# scales_old_new.net
KiCad netlist of a schematic drawn in EAGLE
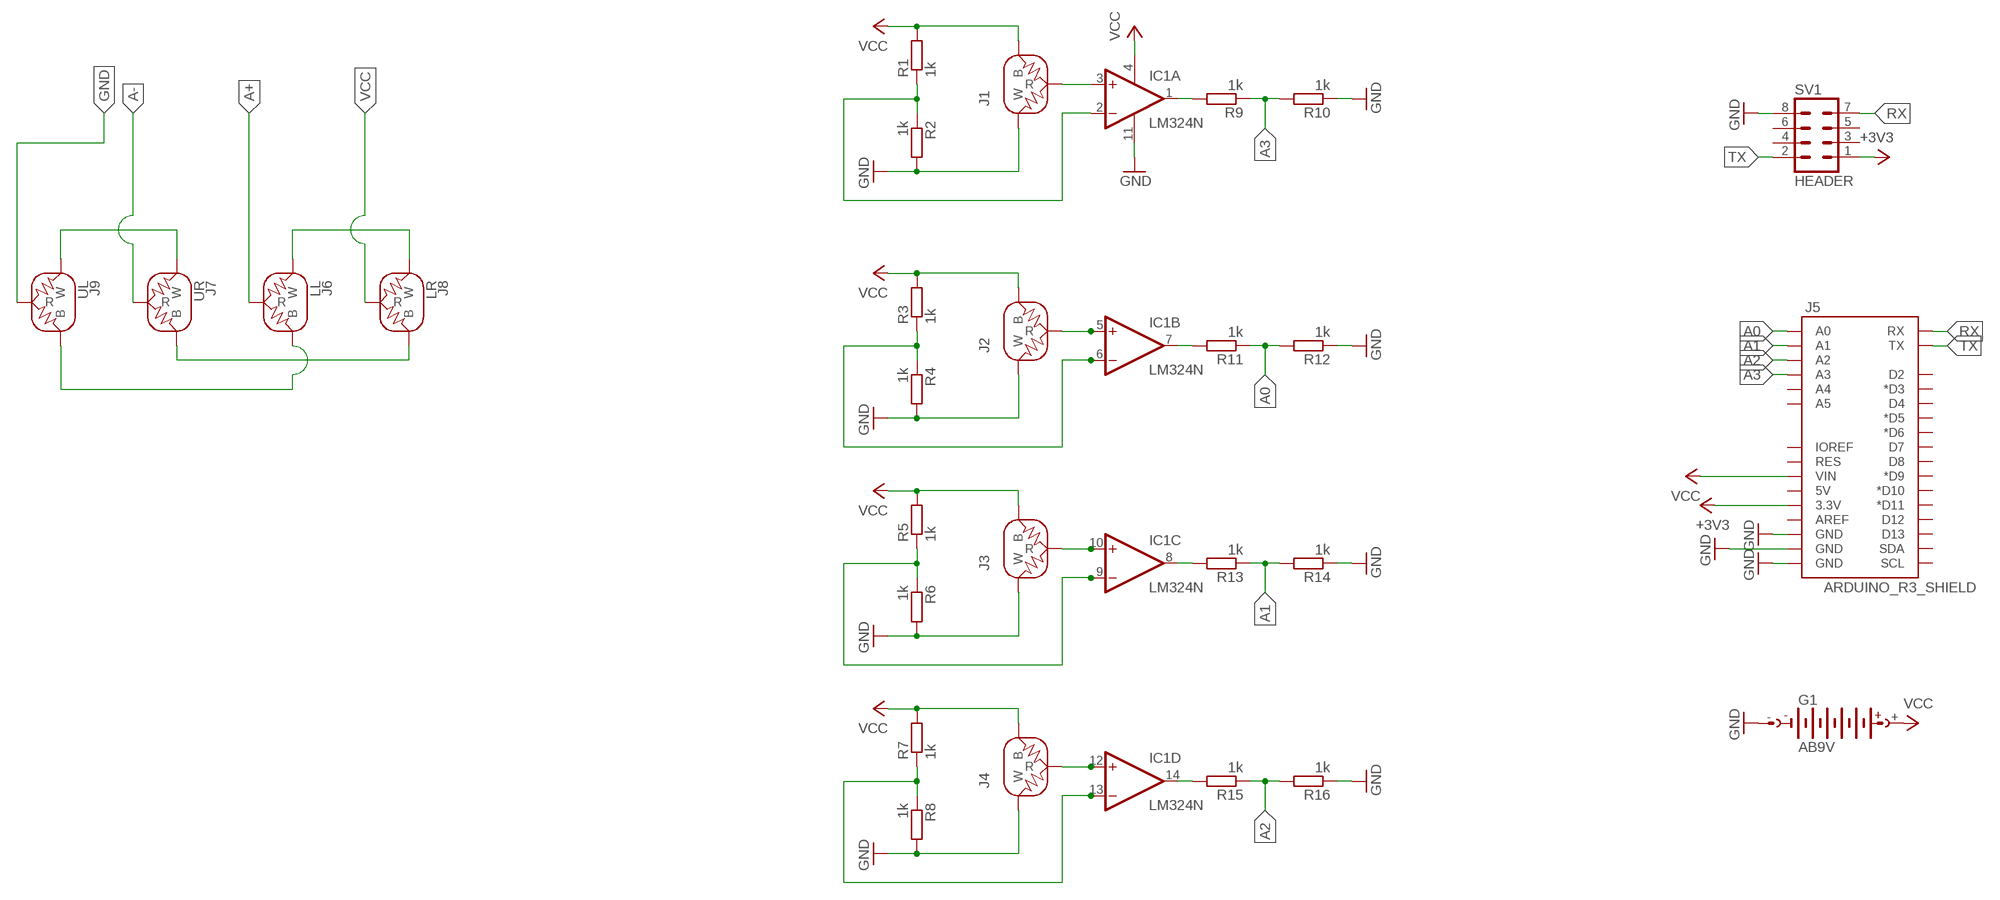
[diagram p0: schematic, sheet 1]

(export (version "E")
  (design (tool "Eeschema 10.0.6"))
  (components
    (comp (ref "G1")
      (value "AB9V")
      (footprint "eagle-import:AB9V")
      (fields (field (name "MF") "MULTICOMP") (field (name "MPN") "440005P"))
      (libsource (lib "eagle-import") (part "AB9V"))
    )
    (comp (ref "IC1")
      (value "LM324N")
      (footprint "eagle-import:DIL14")
      (fields
        (field (name "MF") "STMICROELECTRONICS")
        (field (name "MPN") "LM324AN")
        (field (name "OC_FARNELL") "1467654")
      )
      (libsource (lib "eagle-import") (part "LM324N"))
    )
    (comp (ref "J1")
      (value "LOAD_CELL1X03-PTH")
      (footprint "eagle-import:1X03")
      (libsource (lib "eagle-import") (part "LOAD_CELL1X03-PTH"))
    )
    (comp (ref "J2")
      (value "LOAD_CELL1X03-PTH")
      (footprint "eagle-import:1X03")
      (libsource (lib "eagle-import") (part "LOAD_CELL1X03-PTH"))
    )
    (comp (ref "J3")
      (value "LOAD_CELL1X03-PTH")
      (footprint "eagle-import:1X03")
      (libsource (lib "eagle-import") (part "LOAD_CELL1X03-PTH"))
    )
    (comp (ref "J4")
      (value "LOAD_CELL1X03-PTH")
      (footprint "eagle-import:1X03")
      (libsource (lib "eagle-import") (part "LOAD_CELL1X03-PTH"))
    )
    (comp (ref "J5")
      (value "ARDUINO_R3_SHIELD")
      (footprint "eagle-import:UNO_R3_SHIELD")
      (libsource (lib "eagle-import") (part "ARDUINO_R3_SHIELD"))
    )
    (comp (ref "J6")
      (value "LL")
      (footprint "eagle-import:1X03")
      (libsource (lib "eagle-import") (part "LOAD_CELL1X03-PTH"))
    )
    (comp (ref "J7")
      (value "UR")
      (footprint "eagle-import:1X03")
      (libsource (lib "eagle-import") (part "LOAD_CELL1X03-PTH"))
    )
    (comp (ref "J8")
      (value "LR")
      (footprint "eagle-import:1X03")
      (libsource (lib "eagle-import") (part "LOAD_CELL1X03-PTH"))
    )
    (comp (ref "J9")
      (value "UL")
      (footprint "eagle-import:1X03")
      (libsource (lib "eagle-import") (part "LOAD_CELL1X03-PTH"))
    )
    (comp (ref "R1")
      (value "1k")
      (footprint "eagle-import:0204_5")
      (fields (field (name "MF") "PANASONIC ELECTRONIC COMPONENTS") (field (name "MPN") "ERG1SJ102"))
      (libsource (lib "eagle-import") (part "R-EU_0204/5"))
    )
    (comp (ref "R2")
      (value "1k")
      (footprint "eagle-import:0204_5")
      (fields (field (name "MF") "PANASONIC ELECTRONIC COMPONENTS") (field (name "MPN") "ERG1SJ102"))
      (libsource (lib "eagle-import") (part "R-EU_0204/5"))
    )
    (comp (ref "R3")
      (value "1k")
      (footprint "eagle-import:0204_5")
      (fields (field (name "MF") "PANASONIC ELECTRONIC COMPONENTS") (field (name "MPN") "ERG1SJ102"))
      (libsource (lib "eagle-import") (part "R-EU_0204/5"))
    )
    (comp (ref "R4")
      (value "1k")
      (footprint "eagle-import:0204_5")
      (fields (field (name "MF") "PANASONIC ELECTRONIC COMPONENTS") (field (name "MPN") "ERG1SJ102"))
      (libsource (lib "eagle-import") (part "R-EU_0204/5"))
    )
    (comp (ref "R5")
      (value "1k")
      (footprint "eagle-import:0204_5")
      (fields (field (name "MF") "PANASONIC ELECTRONIC COMPONENTS") (field (name "MPN") "ERG1SJ102"))
      (libsource (lib "eagle-import") (part "R-EU_0204/5"))
    )
    (comp (ref "R6")
      (value "1k")
      (footprint "eagle-import:0204_5")
      (fields (field (name "MF") "PANASONIC ELECTRONIC COMPONENTS") (field (name "MPN") "ERG1SJ102"))
      (libsource (lib "eagle-import") (part "R-EU_0204/5"))
    )
    (comp (ref "R7")
      (value "1k")
      (footprint "eagle-import:0204_5")
      (fields (field (name "MF") "PANASONIC ELECTRONIC COMPONENTS") (field (name "MPN") "ERG1SJ102"))
      (libsource (lib "eagle-import") (part "R-EU_0204/5"))
    )
    (comp (ref "R8")
      (value "1k")
      (footprint "eagle-import:0204_5")
      (fields (field (name "MF") "PANASONIC ELECTRONIC COMPONENTS") (field (name "MPN") "ERG1SJ102"))
      (libsource (lib "eagle-import") (part "R-EU_0204/5"))
    )
    (comp (ref "R9")
      (value "1k")
      (footprint "eagle-import:0204_5")
      (fields (field (name "MF") "PANASONIC ELECTRONIC COMPONENTS") (field (name "MPN") "ERG1SJ102"))
      (libsource (lib "eagle-import") (part "R-EU_0204/5"))
    )
    (comp (ref "R10")
      (value "1k")
      (footprint "eagle-import:0204_5")
      (fields (field (name "MF") "PANASONIC ELECTRONIC COMPONENTS") (field (name "MPN") "ERG1SJ102"))
      (libsource (lib "eagle-import") (part "R-EU_0204/5"))
    )
    (comp (ref "R11")
      (value "1k")
      (footprint "eagle-import:0204_5")
      (fields (field (name "MF") "PANASONIC ELECTRONIC COMPONENTS") (field (name "MPN") "ERG1SJ102"))
      (libsource (lib "eagle-import") (part "R-EU_0204/5"))
    )
    (comp (ref "R12")
      (value "1k")
      (footprint "eagle-import:0204_5")
      (fields (field (name "MF") "PANASONIC ELECTRONIC COMPONENTS") (field (name "MPN") "ERG1SJ102"))
      (libsource (lib "eagle-import") (part "R-EU_0204/5"))
    )
    (comp (ref "R13")
      (value "1k")
      (footprint "eagle-import:0204_5")
      (fields (field (name "MF") "PANASONIC ELECTRONIC COMPONENTS") (field (name "MPN") "ERG1SJ102"))
      (libsource (lib "eagle-import") (part "R-EU_0204/5"))
    )
    (comp (ref "R14")
      (value "1k")
      (footprint "eagle-import:0204_5")
      (fields (field (name "MF") "PANASONIC ELECTRONIC COMPONENTS") (field (name "MPN") "ERG1SJ102"))
      (libsource (lib "eagle-import") (part "R-EU_0204/5"))
    )
    (comp (ref "R15")
      (value "1k")
      (footprint "eagle-import:0204_5")
      (fields (field (name "MF") "PANASONIC ELECTRONIC COMPONENTS") (field (name "MPN") "ERG1SJ102"))
      (libsource (lib "eagle-import") (part "R-EU_0204/5"))
    )
    (comp (ref "R16")
      (value "1k")
      (footprint "eagle-import:0204_5")
      (fields (field (name "MF") "PANASONIC ELECTRONIC COMPONENTS") (field (name "MPN") "ERG1SJ102"))
      (libsource (lib "eagle-import") (part "R-EU_0204/5"))
    )
    (comp (ref "SV1")
      (value "HEADER")
      (footprint "eagle-import:MA04-2")
      (fields
        (field (name "MF") "GLOBAL CONNECTOR TECHNOLOGY")
        (field (name "MPN") "BD060-08-A-N-0230-L-G")
        (field (name "OC_FARNELL") "1798806")
      )
      (libsource (lib "eagle-import") (part "MA04-2"))
    )
  )
  (nets
    (net (code "1") (name "+3V3") (class "Default")
      (node (ref "J5") (pin "3.3V") (pinfunction "3.3V_3.3V") (pintype "bidirectional"))
      (node (ref "SV1") (pin "1") (pinfunction "1_1") (pintype "passive"))
    )
    (net (code "2") (name "A+") (class "Default")
      (node (ref "J6") (pin "3") (pinfunction "R_3") (pintype "passive"))
    )
    (net (code "3") (name "A-") (class "Default")
      (node (ref "J7") (pin "3") (pinfunction "R_3") (pintype "passive"))
    )
    (net (code "4") (name "A0") (class "Default")
      (node (ref "J5") (pin "A0") (pinfunction "A0_A0") (pintype "bidirectional"))
      (node (ref "R11") (pin "1") (pinfunction "1_1") (pintype "passive"))
      (node (ref "R12") (pin "2") (pinfunction "2_2") (pintype "passive"))
    )
    (net (code "5") (name "A1") (class "Default")
      (node (ref "J5") (pin "A1") (pinfunction "A1_A1") (pintype "bidirectional"))
      (node (ref "R13") (pin "1") (pinfunction "1_1") (pintype "passive"))
      (node (ref "R14") (pin "2") (pinfunction "2_2") (pintype "passive"))
    )
    (net (code "6") (name "A2") (class "Default")
      (node (ref "J5") (pin "A2") (pinfunction "A2_A2") (pintype "bidirectional"))
      (node (ref "R15") (pin "1") (pinfunction "1_1") (pintype "passive"))
      (node (ref "R16") (pin "2") (pinfunction "2_2") (pintype "passive"))
    )
    (net (code "7") (name "A3") (class "Default")
      (node (ref "J5") (pin "A3") (pinfunction "A3_A3") (pintype "bidirectional"))
      (node (ref "R10") (pin "2") (pinfunction "2_2") (pintype "passive"))
      (node (ref "R9") (pin "1") (pinfunction "1_1") (pintype "passive"))
    )
    (net (code "8") (name "GND") (class "Default")
      (node (ref "G1") (pin "-") (pinfunction "-_-") (pintype "passive"))
      (node (ref "IC1") (pin "11") (pinfunction "V-_11") (pintype "power_in"))
      (node (ref "J1") (pin "2") (pinfunction "W_2") (pintype "passive"))
      (node (ref "J2") (pin "2") (pinfunction "W_2") (pintype "passive"))
      (node (ref "J3") (pin "2") (pinfunction "W_2") (pintype "passive"))
      (node (ref "J4") (pin "2") (pinfunction "W_2") (pintype "passive"))
      (node (ref "J5") (pin "GND@0") (pinfunction "GND_GND@0") (pintype "bidirectional"))
      (node (ref "J5") (pin "GND@1") (pinfunction "GND_GND@1") (pintype "bidirectional"))
      (node (ref "J5") (pin "GND@2") (pinfunction "GND_GND@2") (pintype "bidirectional"))
      (node (ref "J9") (pin "3") (pinfunction "R_3") (pintype "passive"))
      (node (ref "R10") (pin "1") (pinfunction "1_1") (pintype "passive"))
      (node (ref "R12") (pin "1") (pinfunction "1_1") (pintype "passive"))
      (node (ref "R14") (pin "1") (pinfunction "1_1") (pintype "passive"))
      (node (ref "R16") (pin "1") (pinfunction "1_1") (pintype "passive"))
      (node (ref "R2") (pin "2") (pinfunction "2_2") (pintype "passive"))
      (node (ref "R4") (pin "2") (pinfunction "2_2") (pintype "passive"))
      (node (ref "R6") (pin "2") (pinfunction "2_2") (pintype "passive"))
      (node (ref "R8") (pin "2") (pinfunction "2_2") (pintype "passive"))
      (node (ref "SV1") (pin "8") (pinfunction "8_8") (pintype "passive"))
    )
    (net (code "9") (name "Net-(IC1A-+IN)") (class "Default")
      (node (ref "IC1") (pin "3") (pinfunction "+IN_3") (pintype "input"))
      (node (ref "J1") (pin "3") (pinfunction "R_3") (pintype "passive"))
    )
    (net (code "10") (name "Net-(IC1A--IN)") (class "Default")
      (node (ref "IC1") (pin "2") (pinfunction "-IN_2") (pintype "input"))
      (node (ref "R1") (pin "1") (pinfunction "1_1") (pintype "passive"))
      (node (ref "R2") (pin "1") (pinfunction "1_1") (pintype "passive"))
    )
    (net (code "11") (name "Net-(IC1A-OUT)") (class "Default")
      (node (ref "IC1") (pin "1") (pinfunction "OUT_1") (pintype "output"))
      (node (ref "R9") (pin "2") (pinfunction "2_2") (pintype "passive"))
    )
    (net (code "12") (name "Net-(IC1B-+IN)") (class "Default")
      (node (ref "IC1") (pin "5") (pinfunction "+IN_5") (pintype "input"))
      (node (ref "J2") (pin "3") (pinfunction "R_3") (pintype "passive"))
    )
    (net (code "13") (name "Net-(IC1B--IN)") (class "Default")
      (node (ref "IC1") (pin "6") (pinfunction "-IN_6") (pintype "input"))
      (node (ref "R3") (pin "1") (pinfunction "1_1") (pintype "passive"))
      (node (ref "R4") (pin "1") (pinfunction "1_1") (pintype "passive"))
    )
    (net (code "14") (name "Net-(IC1B-OUT)") (class "Default")
      (node (ref "IC1") (pin "7") (pinfunction "OUT_7") (pintype "output"))
      (node (ref "R11") (pin "2") (pinfunction "2_2") (pintype "passive"))
    )
    (net (code "15") (name "Net-(IC1C-+IN)") (class "Default")
      (node (ref "IC1") (pin "10") (pinfunction "+IN_10") (pintype "input"))
      (node (ref "J3") (pin "3") (pinfunction "R_3") (pintype "passive"))
    )
    (net (code "16") (name "Net-(IC1C--IN)") (class "Default")
      (node (ref "IC1") (pin "9") (pinfunction "-IN_9") (pintype "input"))
      (node (ref "R5") (pin "1") (pinfunction "1_1") (pintype "passive"))
      (node (ref "R6") (pin "1") (pinfunction "1_1") (pintype "passive"))
    )
    (net (code "17") (name "Net-(IC1C-OUT)") (class "Default")
      (node (ref "IC1") (pin "8") (pinfunction "OUT_8") (pintype "output"))
      (node (ref "R13") (pin "2") (pinfunction "2_2") (pintype "passive"))
    )
    (net (code "18") (name "Net-(IC1D-+IN)") (class "Default")
      (node (ref "IC1") (pin "12") (pinfunction "+IN_12") (pintype "input"))
      (node (ref "J4") (pin "3") (pinfunction "R_3") (pintype "passive"))
    )
    (net (code "19") (name "Net-(IC1D--IN)") (class "Default")
      (node (ref "IC1") (pin "13") (pinfunction "-IN_13") (pintype "input"))
      (node (ref "R7") (pin "1") (pinfunction "1_1") (pintype "passive"))
      (node (ref "R8") (pin "1") (pinfunction "1_1") (pintype "passive"))
    )
    (net (code "20") (name "Net-(IC1D-OUT)") (class "Default")
      (node (ref "IC1") (pin "14") (pinfunction "OUT_14") (pintype "output"))
      (node (ref "R15") (pin "2") (pinfunction "2_2") (pintype "passive"))
    )
    (net (code "21") (name "Net-(J6-B)") (class "Default")
      (node (ref "J6") (pin "1") (pinfunction "B_1") (pintype "passive"))
      (node (ref "J9") (pin "1") (pinfunction "B_1") (pintype "passive"))
    )
    (net (code "22") (name "Net-(J6-W)") (class "Default")
      (node (ref "J6") (pin "2") (pinfunction "W_2") (pintype "passive"))
      (node (ref "J8") (pin "2") (pinfunction "W_2") (pintype "passive"))
    )
    (net (code "23") (name "Net-(J7-B)") (class "Default")
      (node (ref "J7") (pin "1") (pinfunction "B_1") (pintype "passive"))
      (node (ref "J8") (pin "1") (pinfunction "B_1") (pintype "passive"))
    )
    (net (code "24") (name "Net-(J7-W)") (class "Default")
      (node (ref "J7") (pin "2") (pinfunction "W_2") (pintype "passive"))
      (node (ref "J9") (pin "2") (pinfunction "W_2") (pintype "passive"))
    )
    (net (code "25") (name "RX") (class "Default")
      (node (ref "J5") (pin "RX") (pinfunction "RX_RX") (pintype "bidirectional"))
      (node (ref "SV1") (pin "7") (pinfunction "7_7") (pintype "passive"))
    )
    (net (code "26") (name "TX") (class "Default")
      (node (ref "J5") (pin "TX") (pinfunction "TX_TX") (pintype "bidirectional"))
      (node (ref "SV1") (pin "2") (pinfunction "2_2") (pintype "passive"))
    )
    (net (code "27") (name "VCC") (class "Default")
      (node (ref "G1") (pin "+") (pinfunction "+_+") (pintype "passive"))
      (node (ref "IC1") (pin "4") (pinfunction "V+_4") (pintype "power_in"))
      (node (ref "J1") (pin "1") (pinfunction "B_1") (pintype "passive"))
      (node (ref "J2") (pin "1") (pinfunction "B_1") (pintype "passive"))
      (node (ref "J3") (pin "1") (pinfunction "B_1") (pintype "passive"))
      (node (ref "J4") (pin "1") (pinfunction "B_1") (pintype "passive"))
      (node (ref "J5") (pin "VIN") (pinfunction "VIN_VIN") (pintype "bidirectional"))
      (node (ref "J8") (pin "3") (pinfunction "R_3") (pintype "passive"))
      (node (ref "R1") (pin "2") (pinfunction "2_2") (pintype "passive"))
      (node (ref "R3") (pin "2") (pinfunction "2_2") (pintype "passive"))
      (node (ref "R5") (pin "2") (pinfunction "2_2") (pintype "passive"))
      (node (ref "R7") (pin "2") (pinfunction "2_2") (pintype "passive"))
    )
    (net (code "28") (name "unconnected-(J5-*D3-PadD3)") (class "Default")
      (node (ref "J5") (pin "D3") (pinfunction "*D3_D3") (pintype "bidirectional"))
    )
    (net (code "29") (name "unconnected-(J5-*D5-PadD5)") (class "Default")
      (node (ref "J5") (pin "D5") (pinfunction "*D5_D5") (pintype "bidirectional"))
    )
    (net (code "30") (name "unconnected-(J5-*D6-PadD6)") (class "Default")
      (node (ref "J5") (pin "D6") (pinfunction "*D6_D6") (pintype "bidirectional"))
    )
    (net (code "31") (name "unconnected-(J5-*D9-PadD9)") (class "Default")
      (node (ref "J5") (pin "D9") (pinfunction "*D9_D9") (pintype "bidirectional"))
    )
    (net (code "32") (name "unconnected-(J5-*D10-PadD10)") (class "Default")
      (node (ref "J5") (pin "D10") (pinfunction "*D10_D10") (pintype "bidirectional"))
    )
    (net (code "33") (name "unconnected-(J5-*D11-PadD11)") (class "Default")
      (node (ref "J5") (pin "D11") (pinfunction "*D11_D11") (pintype "bidirectional"))
    )
    (net (code "34") (name "unconnected-(J5-Pad5V)") (class "Default")
      (node (ref "J5") (pin "5V") (pinfunction "5V_5V") (pintype "bidirectional"))
    )
    (net (code "35") (name "unconnected-(J5-PadA4)") (class "Default")
      (node (ref "J5") (pin "A4") (pinfunction "A4_A4") (pintype "bidirectional"))
    )
    (net (code "36") (name "unconnected-(J5-PadA5)") (class "Default")
      (node (ref "J5") (pin "A5") (pinfunction "A5_A5") (pintype "bidirectional"))
    )
    (net (code "37") (name "unconnected-(J5-PadAREF)") (class "Default")
      (node (ref "J5") (pin "AREF") (pinfunction "AREF_AREF") (pintype "bidirectional"))
    )
    (net (code "38") (name "unconnected-(J5-PadD2)") (class "Default")
      (node (ref "J5") (pin "D2") (pinfunction "D2_D2") (pintype "bidirectional"))
    )
    (net (code "39") (name "unconnected-(J5-PadD4)") (class "Default")
      (node (ref "J5") (pin "D4") (pinfunction "D4_D4") (pintype "bidirectional"))
    )
    (net (code "40") (name "unconnected-(J5-PadD7)") (class "Default")
      (node (ref "J5") (pin "D7") (pinfunction "D7_D7") (pintype "bidirectional"))
    )
    (net (code "41") (name "unconnected-(J5-PadD8)") (class "Default")
      (node (ref "J5") (pin "D8") (pinfunction "D8_D8") (pintype "bidirectional"))
    )
    (net (code "42") (name "unconnected-(J5-PadD12)") (class "Default")
      (node (ref "J5") (pin "D12") (pinfunction "D12_D12") (pintype "bidirectional"))
    )
    (net (code "43") (name "unconnected-(J5-PadD13)") (class "Default")
      (node (ref "J5") (pin "D13") (pinfunction "D13_D13") (pintype "bidirectional"))
    )
    (net (code "44") (name "unconnected-(J5-PadIOREF)") (class "Default")
      (node (ref "J5") (pin "IOREF") (pinfunction "IOREF_IOREF") (pintype "bidirectional"))
    )
    (net (code "45") (name "unconnected-(J5-PadRES)") (class "Default")
      (node (ref "J5") (pin "RES") (pinfunction "RES_RES") (pintype "bidirectional"))
    )
    (net (code "46") (name "unconnected-(J5-PadSCL)") (class "Default")
      (node (ref "J5") (pin "SCL") (pinfunction "SCL_SCL") (pintype "bidirectional"))
    )
    (net (code "47") (name "unconnected-(J5-PadSDA)") (class "Default")
      (node (ref "J5") (pin "SDA") (pinfunction "SDA_SDA") (pintype "bidirectional"))
    )
    (net (code "48") (name "unconnected-(SV1-Pad3)") (class "Default")
      (node (ref "SV1") (pin "3") (pinfunction "3_3") (pintype "passive"))
    )
    (net (code "49") (name "unconnected-(SV1-Pad4)") (class "Default")
      (node (ref "SV1") (pin "4") (pinfunction "4_4") (pintype "passive"))
    )
    (net (code "50") (name "unconnected-(SV1-Pad5)") (class "Default")
      (node (ref "SV1") (pin "5") (pinfunction "5_5") (pintype "passive"))
    )
    (net (code "51") (name "unconnected-(SV1-Pad6)") (class "Default")
      (node (ref "SV1") (pin "6") (pinfunction "6_6") (pintype "passive"))
    )
  )
)
